# 6_uart_esc_i2c.net
KiCad netlist of a schematic drawn in Altium Designer
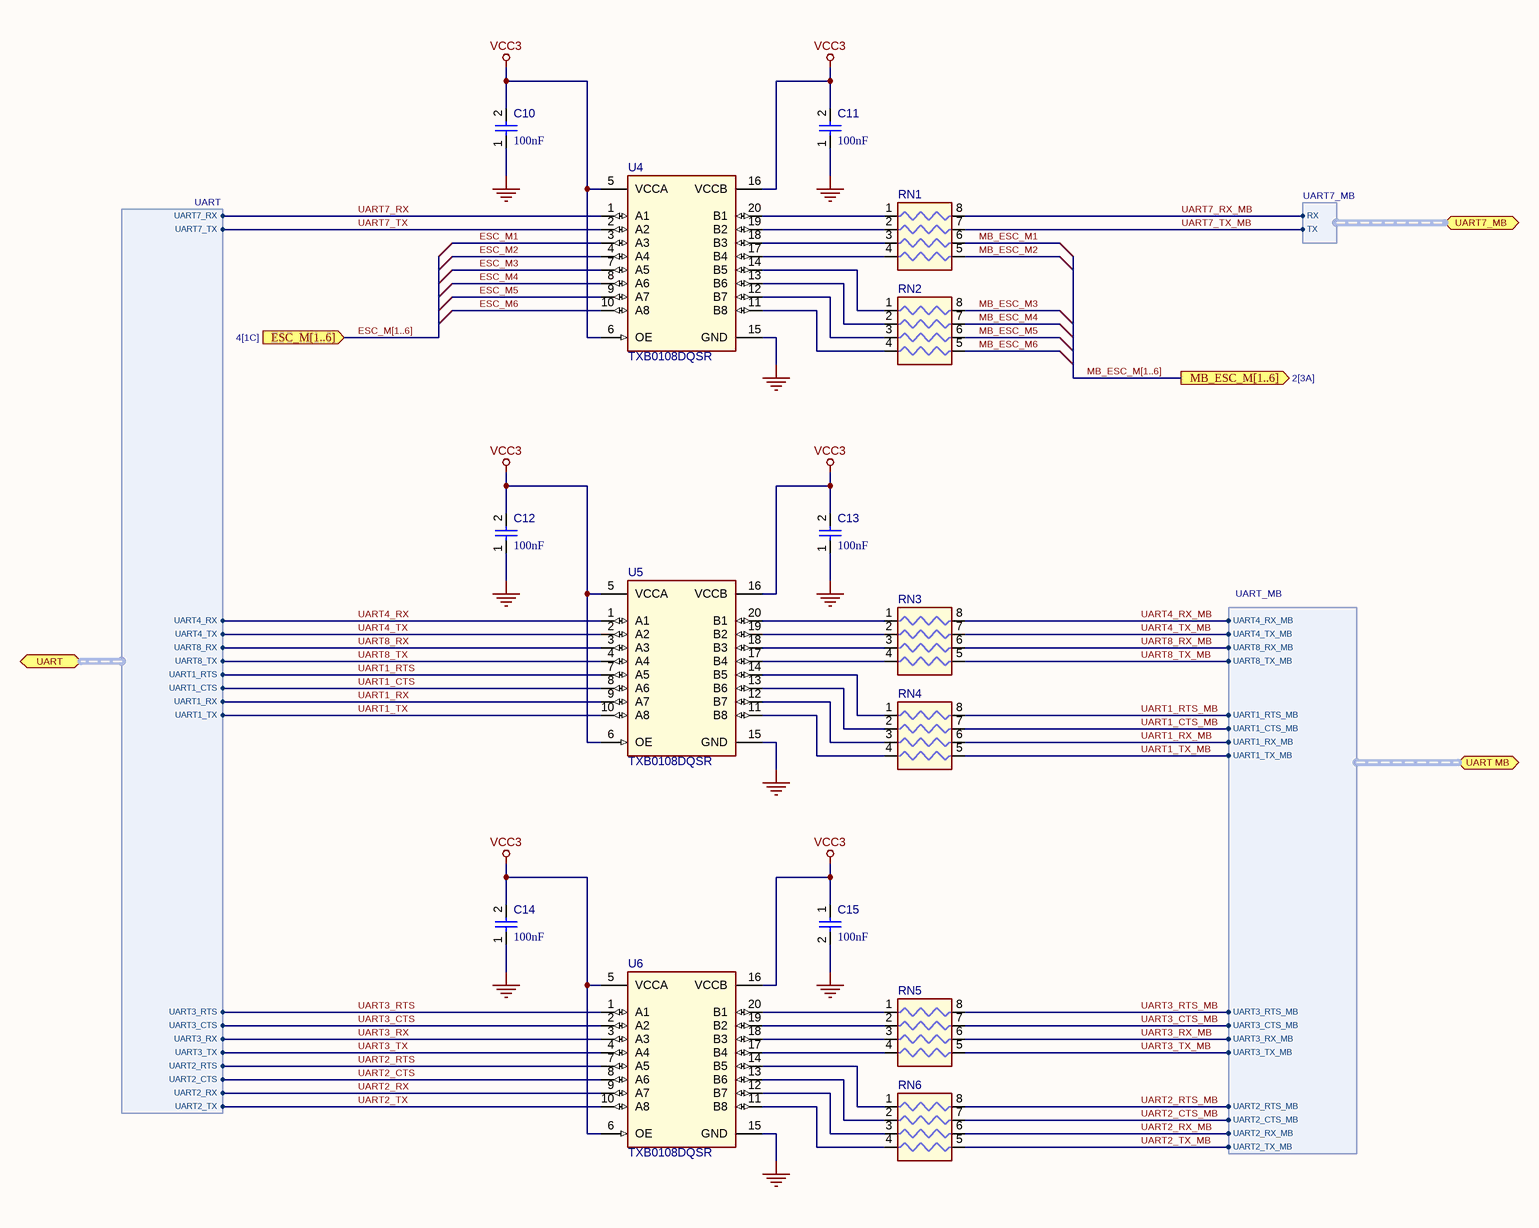
[diagram p0: 6_uart_esc_i2c.SchDoc]

(export (version "E")
  (design (tool "Eeschema 10.0.6"))
  (components
    (comp (ref "C10")
      (value "100nF")
      (footprint "CAPC0402(1005)60_L")
      (description "Chip Capacitor, 100nF +/-20%, 10V, 0402, Thickness 0.6 mm")
      (fields (field (name "TOLERANCE") "20%") (field (name "Comment") "Capacitor 100nF +/-20% 10V 0402"))
      (libsource (lib "<Company> Server") (part "CAP-NP-2"))
    )
    (comp (ref "C11")
      (value "100nF")
      (footprint "CAPC0402(1005)60_L")
      (description "Chip Capacitor, 100nF +/-20%, 10V, 0402, Thickness 0.6 mm")
      (fields (field (name "TOLERANCE") "20%") (field (name "Comment") "Capacitor 100nF +/-20% 10V 0402"))
      (libsource (lib "<Company> Server") (part "CAP-NP-2"))
    )
    (comp (ref "C12")
      (value "100nF")
      (footprint "CAPC0402(1005)60_L")
      (description "Chip Capacitor, 100nF +/-20%, 10V, 0402, Thickness 0.6 mm")
      (fields (field (name "TOLERANCE") "20%") (field (name "Comment") "Capacitor 100nF +/-20% 10V 0402"))
      (libsource (lib "<Company> Server") (part "CAP-NP-2"))
    )
    (comp (ref "C13")
      (value "100nF")
      (footprint "CAPC0402(1005)60_L")
      (description "Chip Capacitor, 100nF +/-20%, 10V, 0402, Thickness 0.6 mm")
      (fields (field (name "TOLERANCE") "20%") (field (name "Comment") "Capacitor 100nF +/-20% 10V 0402"))
      (libsource (lib "<Company> Server") (part "CAP-NP-2"))
    )
    (comp (ref "C14")
      (value "100nF")
      (footprint "CAPC0402(1005)60_L")
      (description "Chip Capacitor, 100nF +/-20%, 10V, 0402, Thickness 0.6 mm")
      (fields (field (name "TOLERANCE") "20%") (field (name "Comment") "Capacitor 100nF +/-20% 10V 0402"))
      (libsource (lib "<Company> Server") (part "CAP-NP-2"))
    )
    (comp (ref "C15")
      (value "100nF")
      (footprint "CAPC0402(1005)60_L")
      (description "Chip Capacitor, 100nF +/-20%, 10V, 0402, Thickness 0.6 mm")
      (fields (field (name "TOLERANCE") "20%") (field (name "Comment") "Capacitor 100nF +/-20% 10V 0402"))
      (libsource (lib "<Company> Server") (part "CAP-NP-2"))
    )
    (comp (ref "RN1")
      (value "Resistor 200R +/-5% 0402 62.5 mW")
      (footprint "Panasonic_EXB28")
      (fields (field (name "TOLERANCE") "5%") (field (name "POWER") "62.5mW"))
      (libsource (lib "<Company> Server") (part "RES-P-4"))
    )
    (comp (ref "RN2")
      (value "Resistor 200R +/-5% 0402 62.5 mW")
      (footprint "Panasonic_EXB28")
      (fields (field (name "TOLERANCE") "5%") (field (name "POWER") "62.5mW"))
      (libsource (lib "<Company> Server") (part "RES-P-4"))
    )
    (comp (ref "RN3")
      (value "Resistor 200R +/-5% 0402 62.5 mW")
      (footprint "Panasonic_EXB28")
      (fields (field (name "TOLERANCE") "5%") (field (name "POWER") "62.5mW"))
      (libsource (lib "<Company> Server") (part "RES-P-4"))
    )
    (comp (ref "RN4")
      (value "Resistor 200R +/-5% 0402 62.5 mW")
      (footprint "Panasonic_EXB28")
      (fields (field (name "TOLERANCE") "5%") (field (name "POWER") "62.5mW"))
      (libsource (lib "<Company> Server") (part "RES-P-4"))
    )
    (comp (ref "RN5")
      (value "Resistor 200R +/-5% 0402 62.5 mW")
      (footprint "Panasonic_EXB28")
      (fields (field (name "TOLERANCE") "5%") (field (name "POWER") "62.5mW"))
      (libsource (lib "<Company> Server") (part "RES-P-4"))
    )
    (comp (ref "RN6")
      (value "Resistor 200R +/-5% 0402 62.5 mW")
      (footprint "Panasonic_EXB28")
      (fields (field (name "TOLERANCE") "5%") (field (name "POWER") "62.5mW"))
      (libsource (lib "<Company> Server") (part "RES-P-4"))
    )
    (comp (ref "U4")
      (value "TXB0108DQSR")
      (footprint "DQS0020A_V")
      (libsource (lib "<Company> Server") (part "CMP-00162-7"))
    )
    (comp (ref "U5")
      (value "TXB0108DQSR")
      (footprint "DQS0020A_V")
      (libsource (lib "<Company> Server") (part "CMP-00162-7"))
    )
    (comp (ref "U6")
      (value "TXB0108DQSR")
      (footprint "DQS0020A_V")
      (libsource (lib "<Company> Server") (part "CMP-00162-7"))
    )
  )
  (nets
    (net (code "4") (name "/ESC_M1") (class "Default")
      (node (ref "U4") (pin "3") (pinfunction "A3_3") (pintype "bidirectional"))
    )
    (net (code "5") (name "/ESC_M2") (class "Default")
      (node (ref "U4") (pin "4") (pinfunction "A4_4") (pintype "bidirectional"))
    )
    (net (code "6") (name "/ESC_M3") (class "Default")
      (node (ref "U4") (pin "7") (pinfunction "A5_7") (pintype "bidirectional"))
    )
    (net (code "7") (name "/ESC_M4") (class "Default")
      (node (ref "U4") (pin "8") (pinfunction "A6_8") (pintype "bidirectional"))
    )
    (net (code "8") (name "/ESC_M5") (class "Default")
      (node (ref "U4") (pin "9") (pinfunction "A7_9") (pintype "bidirectional"))
    )
    (net (code "9") (name "/ESC_M6") (class "Default")
      (node (ref "U4") (pin "10") (pinfunction "A8_10") (pintype "bidirectional"))
    )
    (net (code "11") (name "/MB_ESC_M1") (class "Default")
      (node (ref "RN1") (pin "6") (pinfunction "2_6") (pintype "passive"))
    )
    (net (code "12") (name "/MB_ESC_M2") (class "Default")
      (node (ref "RN1") (pin "5") (pinfunction "2_5") (pintype "passive"))
    )
    (net (code "13") (name "/MB_ESC_M3") (class "Default")
      (node (ref "RN2") (pin "8") (pinfunction "2_8") (pintype "passive"))
    )
    (net (code "14") (name "/MB_ESC_M4") (class "Default")
      (node (ref "RN2") (pin "7") (pinfunction "2_7") (pintype "passive"))
    )
    (net (code "15") (name "/MB_ESC_M5") (class "Default")
      (node (ref "RN2") (pin "6") (pinfunction "2_6") (pintype "passive"))
    )
    (net (code "16") (name "/MB_ESC_M6") (class "Default")
      (node (ref "RN2") (pin "5") (pinfunction "2_5") (pintype "passive"))
    )
    (net (code "18") (name "/UART1_CTS") (class "Default")
      (node (ref "U5") (pin "8") (pinfunction "A6_8") (pintype "bidirectional"))
    )
    (net (code "19") (name "/UART1_CTS_MB") (class "Default")
      (node (ref "RN4") (pin "7") (pinfunction "2_7") (pintype "passive"))
    )
    (net (code "20") (name "/UART1_RTS") (class "Default")
      (node (ref "U5") (pin "7") (pinfunction "A5_7") (pintype "bidirectional"))
    )
    (net (code "21") (name "/UART1_RTS_MB") (class "Default")
      (node (ref "RN4") (pin "8") (pinfunction "2_8") (pintype "passive"))
    )
    (net (code "22") (name "/UART1_RX") (class "Default")
      (node (ref "U5") (pin "9") (pinfunction "A7_9") (pintype "bidirectional"))
    )
    (net (code "23") (name "/UART1_RX_MB") (class "Default")
      (node (ref "RN4") (pin "6") (pinfunction "2_6") (pintype "passive"))
    )
    (net (code "24") (name "/UART1_TX") (class "Default")
      (node (ref "U5") (pin "10") (pinfunction "A8_10") (pintype "bidirectional"))
    )
    (net (code "25") (name "/UART1_TX_MB") (class "Default")
      (node (ref "RN4") (pin "5") (pinfunction "2_5") (pintype "passive"))
    )
    (net (code "26") (name "/UART2_CTS") (class "Default")
      (node (ref "U6") (pin "8") (pinfunction "A6_8") (pintype "bidirectional"))
    )
    (net (code "27") (name "/UART2_CTS_MB") (class "Default")
      (node (ref "RN6") (pin "7") (pinfunction "2_7") (pintype "passive"))
    )
    (net (code "28") (name "/UART2_RTS") (class "Default")
      (node (ref "U6") (pin "7") (pinfunction "A5_7") (pintype "bidirectional"))
    )
    (net (code "29") (name "/UART2_RTS_MB") (class "Default")
      (node (ref "RN6") (pin "8") (pinfunction "2_8") (pintype "passive"))
    )
    (net (code "30") (name "/UART2_RX") (class "Default")
      (node (ref "U6") (pin "9") (pinfunction "A7_9") (pintype "bidirectional"))
    )
    (net (code "31") (name "/UART2_RX_MB") (class "Default")
      (node (ref "RN6") (pin "6") (pinfunction "2_6") (pintype "passive"))
    )
    (net (code "32") (name "/UART2_TX") (class "Default")
      (node (ref "U6") (pin "10") (pinfunction "A8_10") (pintype "bidirectional"))
    )
    (net (code "33") (name "/UART2_TX_MB") (class "Default")
      (node (ref "RN6") (pin "5") (pinfunction "2_5") (pintype "passive"))
    )
    (net (code "34") (name "/UART3_CTS") (class "Default")
      (node (ref "U6") (pin "2") (pinfunction "A2_2") (pintype "bidirectional"))
    )
    (net (code "35") (name "/UART3_CTS_MB") (class "Default")
      (node (ref "RN5") (pin "7") (pinfunction "2_7") (pintype "passive"))
    )
    (net (code "36") (name "/UART3_RTS") (class "Default")
      (node (ref "U6") (pin "1") (pinfunction "A1_1") (pintype "bidirectional"))
    )
    (net (code "37") (name "/UART3_RTS_MB") (class "Default")
      (node (ref "RN5") (pin "8") (pinfunction "2_8") (pintype "passive"))
    )
    (net (code "38") (name "/UART3_RX") (class "Default")
      (node (ref "U6") (pin "3") (pinfunction "A3_3") (pintype "bidirectional"))
    )
    (net (code "39") (name "/UART3_RX_MB") (class "Default")
      (node (ref "RN5") (pin "6") (pinfunction "2_6") (pintype "passive"))
    )
    (net (code "40") (name "/UART3_TX") (class "Default")
      (node (ref "U6") (pin "4") (pinfunction "A4_4") (pintype "bidirectional"))
    )
    (net (code "41") (name "/UART3_TX_MB") (class "Default")
      (node (ref "RN5") (pin "5") (pinfunction "2_5") (pintype "passive"))
    )
    (net (code "42") (name "/UART4_RX") (class "Default")
      (node (ref "U5") (pin "1") (pinfunction "A1_1") (pintype "bidirectional"))
    )
    (net (code "43") (name "/UART4_RX_MB") (class "Default")
      (node (ref "RN3") (pin "8") (pinfunction "2_8") (pintype "passive"))
    )
    (net (code "44") (name "/UART4_TX") (class "Default")
      (node (ref "U5") (pin "2") (pinfunction "A2_2") (pintype "bidirectional"))
    )
    (net (code "45") (name "/UART4_TX_MB") (class "Default")
      (node (ref "RN3") (pin "7") (pinfunction "2_7") (pintype "passive"))
    )
    (net (code "46") (name "/UART7_RX") (class "Default")
      (node (ref "U4") (pin "1") (pinfunction "A1_1") (pintype "bidirectional"))
    )
    (net (code "47") (name "/UART7_RX_MB") (class "Default")
      (node (ref "RN1") (pin "8") (pinfunction "2_8") (pintype "passive"))
    )
    (net (code "48") (name "/UART7_TX") (class "Default")
      (node (ref "U4") (pin "2") (pinfunction "A2_2") (pintype "bidirectional"))
    )
    (net (code "49") (name "/UART7_TX_MB") (class "Default")
      (node (ref "RN1") (pin "7") (pinfunction "2_7") (pintype "passive"))
    )
    (net (code "50") (name "/UART8_RX") (class "Default")
      (node (ref "U5") (pin "3") (pinfunction "A3_3") (pintype "bidirectional"))
    )
    (net (code "51") (name "/UART8_RX_MB") (class "Default")
      (node (ref "RN3") (pin "6") (pinfunction "2_6") (pintype "passive"))
    )
    (net (code "52") (name "/UART8_TX") (class "Default")
      (node (ref "U5") (pin "4") (pinfunction "A4_4") (pintype "bidirectional"))
    )
    (net (code "53") (name "/UART8_TX_MB") (class "Default")
      (node (ref "RN3") (pin "5") (pinfunction "2_5") (pintype "passive"))
    )
    (net (code "57") (name "GND") (class "Default")
      (node (ref "C10") (pin "1") (pinfunction "1_1") (pintype "passive"))
      (node (ref "C11") (pin "1") (pinfunction "1_1") (pintype "passive"))
      (node (ref "C12") (pin "1") (pinfunction "1_1") (pintype "passive"))
      (node (ref "C13") (pin "1") (pinfunction "1_1") (pintype "passive"))
      (node (ref "C14") (pin "1") (pinfunction "1_1") (pintype "passive"))
      (node (ref "C15") (pin "2") (pinfunction "2_2") (pintype "passive"))
      (node (ref "U4") (pin "15") (pinfunction "GND_15") (pintype "power_in"))
      (node (ref "U5") (pin "15") (pinfunction "GND_15") (pintype "power_in"))
      (node (ref "U6") (pin "15") (pinfunction "GND_15") (pintype "power_in"))
    )
    (net (code "58") (name "Net-(U4-B1)") (class "Default")
      (node (ref "RN1") (pin "1") (pinfunction "1_1") (pintype "passive"))
      (node (ref "U4") (pin "20") (pinfunction "B1_20") (pintype "bidirectional"))
    )
    (net (code "59") (name "Net-(U4-B2)") (class "Default")
      (node (ref "RN1") (pin "2") (pinfunction "1_2") (pintype "passive"))
      (node (ref "U4") (pin "19") (pinfunction "B2_19") (pintype "bidirectional"))
    )
    (net (code "60") (name "Net-(U4-B3)") (class "Default")
      (node (ref "RN1") (pin "3") (pinfunction "1_3") (pintype "passive"))
      (node (ref "U4") (pin "18") (pinfunction "B3_18") (pintype "bidirectional"))
    )
    (net (code "61") (name "Net-(U4-B4)") (class "Default")
      (node (ref "RN1") (pin "4") (pinfunction "1_4") (pintype "passive"))
      (node (ref "U4") (pin "17") (pinfunction "B4_17") (pintype "bidirectional"))
    )
    (net (code "62") (name "Net-(U4-B5)") (class "Default")
      (node (ref "RN2") (pin "1") (pinfunction "1_1") (pintype "passive"))
      (node (ref "U4") (pin "14") (pinfunction "B5_14") (pintype "bidirectional"))
    )
    (net (code "63") (name "Net-(U4-B6)") (class "Default")
      (node (ref "RN2") (pin "2") (pinfunction "1_2") (pintype "passive"))
      (node (ref "U4") (pin "13") (pinfunction "B6_13") (pintype "bidirectional"))
    )
    (net (code "64") (name "Net-(U4-B7)") (class "Default")
      (node (ref "RN2") (pin "3") (pinfunction "1_3") (pintype "passive"))
      (node (ref "U4") (pin "12") (pinfunction "B7_12") (pintype "bidirectional"))
    )
    (net (code "65") (name "Net-(U4-B8)") (class "Default")
      (node (ref "RN2") (pin "4") (pinfunction "1_4") (pintype "passive"))
      (node (ref "U4") (pin "11") (pinfunction "B8_11") (pintype "bidirectional"))
    )
    (net (code "66") (name "Net-(U5-B1)") (class "Default")
      (node (ref "RN3") (pin "1") (pinfunction "1_1") (pintype "passive"))
      (node (ref "U5") (pin "20") (pinfunction "B1_20") (pintype "bidirectional"))
    )
    (net (code "67") (name "Net-(U5-B2)") (class "Default")
      (node (ref "RN3") (pin "2") (pinfunction "1_2") (pintype "passive"))
      (node (ref "U5") (pin "19") (pinfunction "B2_19") (pintype "bidirectional"))
    )
    (net (code "68") (name "Net-(U5-B3)") (class "Default")
      (node (ref "RN3") (pin "3") (pinfunction "1_3") (pintype "passive"))
      (node (ref "U5") (pin "18") (pinfunction "B3_18") (pintype "bidirectional"))
    )
    (net (code "69") (name "Net-(U5-B4)") (class "Default")
      (node (ref "RN3") (pin "4") (pinfunction "1_4") (pintype "passive"))
      (node (ref "U5") (pin "17") (pinfunction "B4_17") (pintype "bidirectional"))
    )
    (net (code "70") (name "Net-(U5-B5)") (class "Default")
      (node (ref "RN4") (pin "1") (pinfunction "1_1") (pintype "passive"))
      (node (ref "U5") (pin "14") (pinfunction "B5_14") (pintype "bidirectional"))
    )
    (net (code "71") (name "Net-(U5-B6)") (class "Default")
      (node (ref "RN4") (pin "2") (pinfunction "1_2") (pintype "passive"))
      (node (ref "U5") (pin "13") (pinfunction "B6_13") (pintype "bidirectional"))
    )
    (net (code "72") (name "Net-(U5-B7)") (class "Default")
      (node (ref "RN4") (pin "3") (pinfunction "1_3") (pintype "passive"))
      (node (ref "U5") (pin "12") (pinfunction "B7_12") (pintype "bidirectional"))
    )
    (net (code "73") (name "Net-(U5-B8)") (class "Default")
      (node (ref "RN4") (pin "4") (pinfunction "1_4") (pintype "passive"))
      (node (ref "U5") (pin "11") (pinfunction "B8_11") (pintype "bidirectional"))
    )
    (net (code "74") (name "Net-(U6-B1)") (class "Default")
      (node (ref "RN5") (pin "1") (pinfunction "1_1") (pintype "passive"))
      (node (ref "U6") (pin "20") (pinfunction "B1_20") (pintype "bidirectional"))
    )
    (net (code "75") (name "Net-(U6-B2)") (class "Default")
      (node (ref "RN5") (pin "2") (pinfunction "1_2") (pintype "passive"))
      (node (ref "U6") (pin "19") (pinfunction "B2_19") (pintype "bidirectional"))
    )
    (net (code "76") (name "Net-(U6-B3)") (class "Default")
      (node (ref "RN5") (pin "3") (pinfunction "1_3") (pintype "passive"))
      (node (ref "U6") (pin "18") (pinfunction "B3_18") (pintype "bidirectional"))
    )
    (net (code "77") (name "Net-(U6-B4)") (class "Default")
      (node (ref "RN5") (pin "4") (pinfunction "1_4") (pintype "passive"))
      (node (ref "U6") (pin "17") (pinfunction "B4_17") (pintype "bidirectional"))
    )
    (net (code "78") (name "Net-(U6-B5)") (class "Default")
      (node (ref "RN6") (pin "1") (pinfunction "1_1") (pintype "passive"))
      (node (ref "U6") (pin "14") (pinfunction "B5_14") (pintype "bidirectional"))
    )
    (net (code "79") (name "Net-(U6-B6)") (class "Default")
      (node (ref "RN6") (pin "2") (pinfunction "1_2") (pintype "passive"))
      (node (ref "U6") (pin "13") (pinfunction "B6_13") (pintype "bidirectional"))
    )
    (net (code "80") (name "Net-(U6-B7)") (class "Default")
      (node (ref "RN6") (pin "3") (pinfunction "1_3") (pintype "passive"))
      (node (ref "U6") (pin "12") (pinfunction "B7_12") (pintype "bidirectional"))
    )
    (net (code "81") (name "Net-(U6-B8)") (class "Default")
      (node (ref "RN6") (pin "4") (pinfunction "1_4") (pintype "passive"))
      (node (ref "U6") (pin "11") (pinfunction "B8_11") (pintype "bidirectional"))
    )
    (net (code "82") (name "VCC3") (class "Default")
      (node (ref "C10") (pin "2") (pinfunction "2_2") (pintype "passive"))
      (node (ref "C11") (pin "2") (pinfunction "2_2") (pintype "passive"))
      (node (ref "C12") (pin "2") (pinfunction "2_2") (pintype "passive"))
      (node (ref "C13") (pin "2") (pinfunction "2_2") (pintype "passive"))
      (node (ref "C14") (pin "2") (pinfunction "2_2") (pintype "passive"))
      (node (ref "C15") (pin "1") (pinfunction "1_1") (pintype "passive"))
      (node (ref "U4") (pin "16") (pinfunction "VCCB_16") (pintype "power_in"))
      (node (ref "U4") (pin "5") (pinfunction "VCCA_5") (pintype "power_in"))
      (node (ref "U4") (pin "6") (pinfunction "OE_6") (pintype "input"))
      (node (ref "U5") (pin "16") (pinfunction "VCCB_16") (pintype "power_in"))
      (node (ref "U5") (pin "5") (pinfunction "VCCA_5") (pintype "power_in"))
      (node (ref "U5") (pin "6") (pinfunction "OE_6") (pintype "input"))
      (node (ref "U6") (pin "16") (pinfunction "VCCB_16") (pintype "power_in"))
      (node (ref "U6") (pin "5") (pinfunction "VCCA_5") (pintype "power_in"))
      (node (ref "U6") (pin "6") (pinfunction "OE_6") (pintype "input"))
    )
  )
)
